# front_pane_-_v2.net
KiCad netlist of a schematic drawn in EAGLE
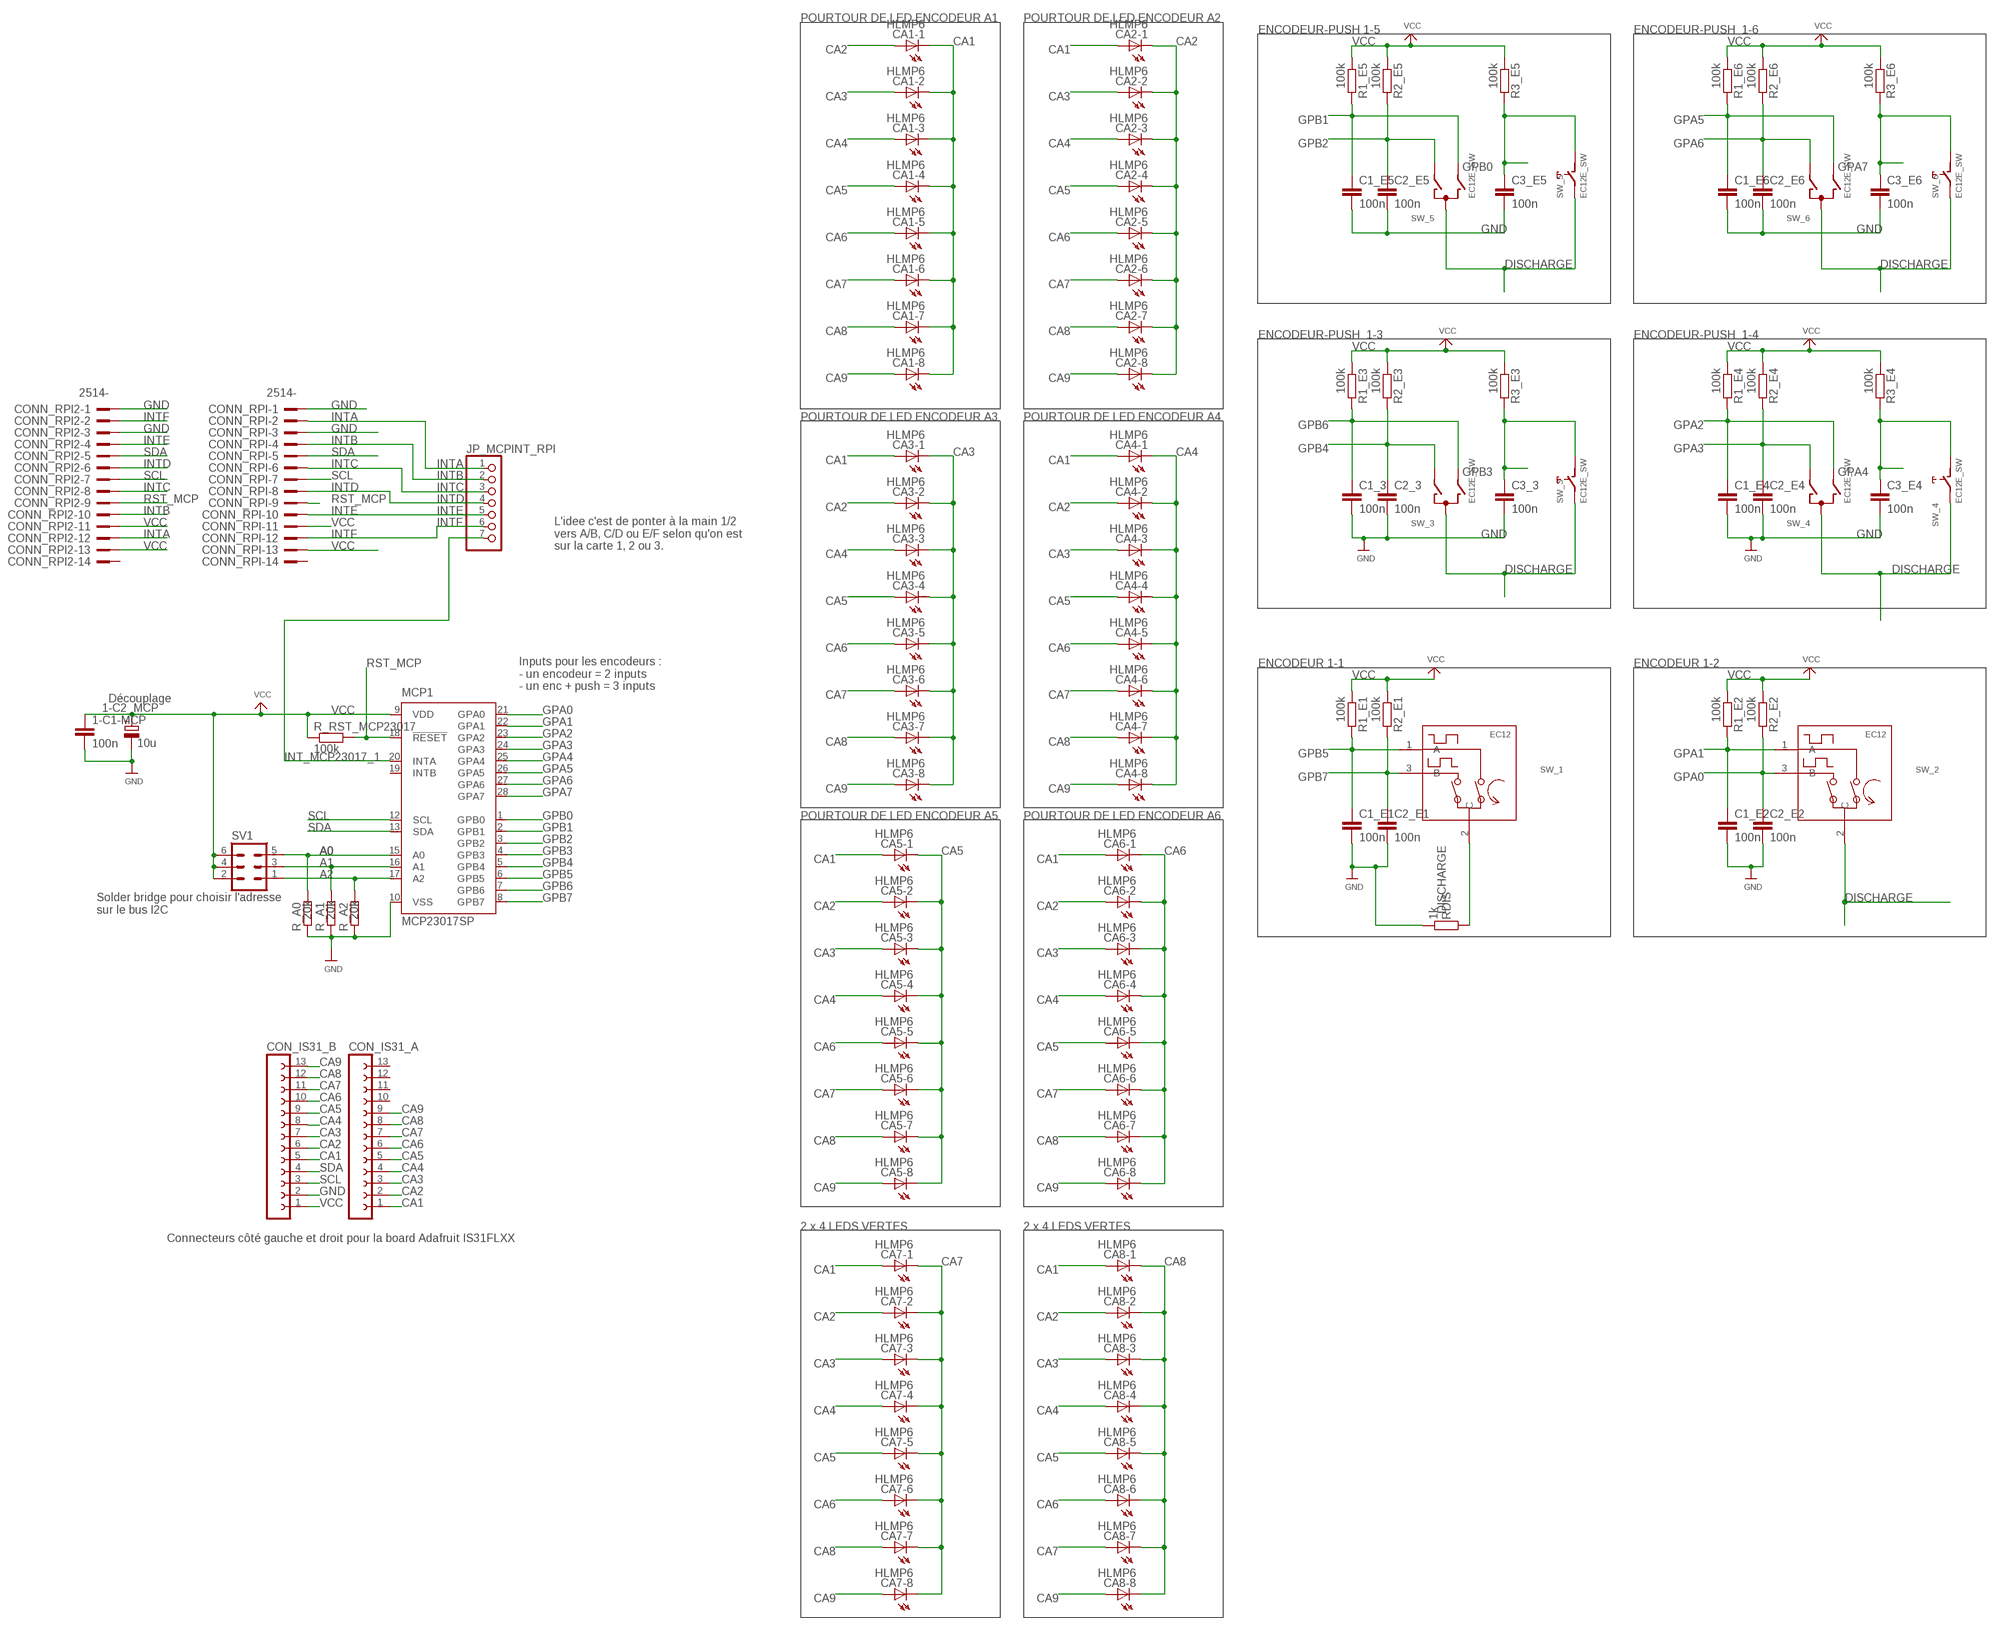
[diagram p0: schematic, sheet 1]

(export (version "E")
  (design (tool "Eeschema 10.0.6"))
  (components
    (comp (ref "1-C1-MCP")
      (value "100n")
      (footprint "eagle-import:C025-024X044")
      (libsource (lib "eagle-import") (part "C-EU025-024X044"))
    )
    (comp (ref "1-C2_MCP")
      (value "10u")
      (footprint "eagle-import:B45181B")
      (libsource (lib "eagle-import") (part "CPOL-EUB45181B"))
    )
    (comp (ref "C1_3")
      (value "100n")
      (footprint "eagle-import:C025-024X044")
      (libsource (lib "eagle-import") (part "C-EU025-024X044"))
    )
    (comp (ref "C1_E1")
      (value "100n")
      (footprint "eagle-import:C025-024X044")
      (libsource (lib "eagle-import") (part "C-EU025-024X044"))
    )
    (comp (ref "C1_E2")
      (value "100n")
      (footprint "eagle-import:C025-024X044")
      (libsource (lib "eagle-import") (part "C-EU025-024X044"))
    )
    (comp (ref "C1_E4")
      (value "100n")
      (footprint "eagle-import:C050-024X044")
      (libsource (lib "eagle-import") (part "C-EU050-024X044"))
    )
    (comp (ref "C1_E5")
      (value "100n")
      (footprint "eagle-import:C025-024X044")
      (libsource (lib "eagle-import") (part "C-EU025-024X044"))
    )
    (comp (ref "C1_E6")
      (value "100n")
      (footprint "eagle-import:C025-024X044")
      (libsource (lib "eagle-import") (part "C-EU025-024X044"))
    )
    (comp (ref "C2_3")
      (value "100n")
      (footprint "eagle-import:C025-024X044")
      (libsource (lib "eagle-import") (part "C-EU025-024X044"))
    )
    (comp (ref "C2_E1")
      (value "100n")
      (footprint "eagle-import:C025-024X044")
      (libsource (lib "eagle-import") (part "C-EU025-024X044"))
    )
    (comp (ref "C2_E2")
      (value "100n")
      (footprint "eagle-import:C025-024X044")
      (libsource (lib "eagle-import") (part "C-EU025-024X044"))
    )
    (comp (ref "C2_E4")
      (value "100n")
      (footprint "eagle-import:C025-024X044")
      (libsource (lib "eagle-import") (part "C-EU025-024X044"))
    )
    (comp (ref "C2_E5")
      (value "100n")
      (footprint "eagle-import:C025-024X044")
      (libsource (lib "eagle-import") (part "C-EU025-024X044"))
    )
    (comp (ref "C2_E6")
      (value "100n")
      (footprint "eagle-import:C025-024X044")
      (libsource (lib "eagle-import") (part "C-EU025-024X044"))
    )
    (comp (ref "C3_3")
      (value "100n")
      (footprint "eagle-import:C025-024X044")
      (libsource (lib "eagle-import") (part "C-EU025-024X044"))
    )
    (comp (ref "C3_E4")
      (value "100n")
      (footprint "eagle-import:C025-024X044")
      (libsource (lib "eagle-import") (part "C-EU025-024X044"))
    )
    (comp (ref "C3_E5")
      (value "100n")
      (footprint "eagle-import:C025-024X044")
      (libsource (lib "eagle-import") (part "C-EU025-024X044"))
    )
    (comp (ref "C3_E6")
      (value "100n")
      (footprint "eagle-import:C025-024X044")
      (libsource (lib "eagle-import") (part "C-EU025-024X044"))
    )
    (comp (ref "CA1-1")
      (value "HLMP6")
      (footprint "eagle-import:HLMP6")
      (fields (field (name "MF") "AGILENT TECHNOLOGIES") (field (name "MPN") "HLMP-6500"))
      (libsource (lib "eagle-import") (part "HLMP6"))
    )
    (comp (ref "CA1-2")
      (value "HLMP6")
      (footprint "eagle-import:HLMP6")
      (fields (field (name "MF") "AGILENT TECHNOLOGIES") (field (name "MPN") "HLMP-6500"))
      (libsource (lib "eagle-import") (part "HLMP6"))
    )
    (comp (ref "CA1-3")
      (value "HLMP6")
      (footprint "eagle-import:HLMP6")
      (fields (field (name "MF") "AGILENT TECHNOLOGIES") (field (name "MPN") "HLMP-6500"))
      (libsource (lib "eagle-import") (part "HLMP6"))
    )
    (comp (ref "CA1-4")
      (value "HLMP6")
      (footprint "eagle-import:HLMP6")
      (fields (field (name "MF") "AGILENT TECHNOLOGIES") (field (name "MPN") "HLMP-6500"))
      (libsource (lib "eagle-import") (part "HLMP6"))
    )
    (comp (ref "CA1-5")
      (value "HLMP6")
      (footprint "eagle-import:HLMP6")
      (fields (field (name "MF") "AGILENT TECHNOLOGIES") (field (name "MPN") "HLMP-6500"))
      (libsource (lib "eagle-import") (part "HLMP6"))
    )
    (comp (ref "CA1-6")
      (value "HLMP6")
      (footprint "eagle-import:HLMP6")
      (fields (field (name "MF") "AGILENT TECHNOLOGIES") (field (name "MPN") "HLMP-6500"))
      (libsource (lib "eagle-import") (part "HLMP6"))
    )
    (comp (ref "CA1-7")
      (value "HLMP6")
      (footprint "eagle-import:HLMP6")
      (fields (field (name "MF") "AGILENT TECHNOLOGIES") (field (name "MPN") "HLMP-6500"))
      (libsource (lib "eagle-import") (part "HLMP6"))
    )
    (comp (ref "CA1-8")
      (value "HLMP6")
      (footprint "eagle-import:HLMP6")
      (fields (field (name "MF") "AGILENT TECHNOLOGIES") (field (name "MPN") "HLMP-6500"))
      (libsource (lib "eagle-import") (part "HLMP6"))
    )
    (comp (ref "CA2-1")
      (value "HLMP6")
      (footprint "eagle-import:HLMP6")
      (fields (field (name "MF") "AGILENT TECHNOLOGIES") (field (name "MPN") "HLMP-6500"))
      (libsource (lib "eagle-import") (part "HLMP6"))
    )
    (comp (ref "CA2-2")
      (value "HLMP6")
      (footprint "eagle-import:HLMP6")
      (fields (field (name "MF") "AGILENT TECHNOLOGIES") (field (name "MPN") "HLMP-6500"))
      (libsource (lib "eagle-import") (part "HLMP6"))
    )
    (comp (ref "CA2-3")
      (value "HLMP6")
      (footprint "eagle-import:HLMP6")
      (fields (field (name "MF") "AGILENT TECHNOLOGIES") (field (name "MPN") "HLMP-6500"))
      (libsource (lib "eagle-import") (part "HLMP6"))
    )
    (comp (ref "CA2-4")
      (value "HLMP6")
      (footprint "eagle-import:HLMP6")
      (fields (field (name "MF") "AGILENT TECHNOLOGIES") (field (name "MPN") "HLMP-6500"))
      (libsource (lib "eagle-import") (part "HLMP6"))
    )
    (comp (ref "CA2-5")
      (value "HLMP6")
      (footprint "eagle-import:HLMP6")
      (fields (field (name "MF") "AGILENT TECHNOLOGIES") (field (name "MPN") "HLMP-6500"))
      (libsource (lib "eagle-import") (part "HLMP6"))
    )
    (comp (ref "CA2-6")
      (value "HLMP6")
      (footprint "eagle-import:HLMP6")
      (fields (field (name "MF") "AGILENT TECHNOLOGIES") (field (name "MPN") "HLMP-6500"))
      (libsource (lib "eagle-import") (part "HLMP6"))
    )
    (comp (ref "CA2-7")
      (value "HLMP6")
      (footprint "eagle-import:HLMP6")
      (fields (field (name "MF") "AGILENT TECHNOLOGIES") (field (name "MPN") "HLMP-6500"))
      (libsource (lib "eagle-import") (part "HLMP6"))
    )
    (comp (ref "CA2-8")
      (value "HLMP6")
      (footprint "eagle-import:HLMP6")
      (fields (field (name "MF") "AGILENT TECHNOLOGIES") (field (name "MPN") "HLMP-6500"))
      (libsource (lib "eagle-import") (part "HLMP6"))
    )
    (comp (ref "CA3-1")
      (value "HLMP6")
      (footprint "eagle-import:HLMP6")
      (fields (field (name "MF") "AGILENT TECHNOLOGIES") (field (name "MPN") "HLMP-6500"))
      (libsource (lib "eagle-import") (part "HLMP6"))
    )
    (comp (ref "CA3-2")
      (value "HLMP6")
      (footprint "eagle-import:HLMP6")
      (fields (field (name "MF") "AGILENT TECHNOLOGIES") (field (name "MPN") "HLMP-6500"))
      (libsource (lib "eagle-import") (part "HLMP6"))
    )
    (comp (ref "CA3-3")
      (value "HLMP6")
      (footprint "eagle-import:HLMP6")
      (fields (field (name "MF") "AGILENT TECHNOLOGIES") (field (name "MPN") "HLMP-6500"))
      (libsource (lib "eagle-import") (part "HLMP6"))
    )
    (comp (ref "CA3-4")
      (value "HLMP6")
      (footprint "eagle-import:HLMP6")
      (fields (field (name "MF") "AGILENT TECHNOLOGIES") (field (name "MPN") "HLMP-6500"))
      (libsource (lib "eagle-import") (part "HLMP6"))
    )
    (comp (ref "CA3-5")
      (value "HLMP6")
      (footprint "eagle-import:HLMP6")
      (fields (field (name "MF") "AGILENT TECHNOLOGIES") (field (name "MPN") "HLMP-6500"))
      (libsource (lib "eagle-import") (part "HLMP6"))
    )
    (comp (ref "CA3-6")
      (value "HLMP6")
      (footprint "eagle-import:HLMP6")
      (fields (field (name "MF") "AGILENT TECHNOLOGIES") (field (name "MPN") "HLMP-6500"))
      (libsource (lib "eagle-import") (part "HLMP6"))
    )
    (comp (ref "CA3-7")
      (value "HLMP6")
      (footprint "eagle-import:HLMP6")
      (fields (field (name "MF") "AGILENT TECHNOLOGIES") (field (name "MPN") "HLMP-6500"))
      (libsource (lib "eagle-import") (part "HLMP6"))
    )
    (comp (ref "CA3-8")
      (value "HLMP6")
      (footprint "eagle-import:HLMP6")
      (fields (field (name "MF") "AGILENT TECHNOLOGIES") (field (name "MPN") "HLMP-6500"))
      (libsource (lib "eagle-import") (part "HLMP6"))
    )
    (comp (ref "CA4-1")
      (value "HLMP6")
      (footprint "eagle-import:HLMP6")
      (fields (field (name "MF") "AGILENT TECHNOLOGIES") (field (name "MPN") "HLMP-6500"))
      (libsource (lib "eagle-import") (part "HLMP6"))
    )
    (comp (ref "CA4-2")
      (value "HLMP6")
      (footprint "eagle-import:HLMP6")
      (fields (field (name "MF") "AGILENT TECHNOLOGIES") (field (name "MPN") "HLMP-6500"))
      (libsource (lib "eagle-import") (part "HLMP6"))
    )
    (comp (ref "CA4-3")
      (value "HLMP6")
      (footprint "eagle-import:HLMP6")
      (fields (field (name "MF") "AGILENT TECHNOLOGIES") (field (name "MPN") "HLMP-6500"))
      (libsource (lib "eagle-import") (part "HLMP6"))
    )
    (comp (ref "CA4-4")
      (value "HLMP6")
      (footprint "eagle-import:HLMP6")
      (fields (field (name "MF") "AGILENT TECHNOLOGIES") (field (name "MPN") "HLMP-6500"))
      (libsource (lib "eagle-import") (part "HLMP6"))
    )
    (comp (ref "CA4-5")
      (value "HLMP6")
      (footprint "eagle-import:HLMP6")
      (fields (field (name "MF") "AGILENT TECHNOLOGIES") (field (name "MPN") "HLMP-6500"))
      (libsource (lib "eagle-import") (part "HLMP6"))
    )
    (comp (ref "CA4-6")
      (value "HLMP6")
      (footprint "eagle-import:HLMP6")
      (fields (field (name "MF") "AGILENT TECHNOLOGIES") (field (name "MPN") "HLMP-6500"))
      (libsource (lib "eagle-import") (part "HLMP6"))
    )
    (comp (ref "CA4-7")
      (value "HLMP6")
      (footprint "eagle-import:HLMP6")
      (fields (field (name "MF") "AGILENT TECHNOLOGIES") (field (name "MPN") "HLMP-6500"))
      (libsource (lib "eagle-import") (part "HLMP6"))
    )
    (comp (ref "CA4-8")
      (value "HLMP6")
      (footprint "eagle-import:HLMP6")
      (fields (field (name "MF") "AGILENT TECHNOLOGIES") (field (name "MPN") "HLMP-6500"))
      (libsource (lib "eagle-import") (part "HLMP6"))
    )
    (comp (ref "CA5-1")
      (value "HLMP6")
      (footprint "eagle-import:HLMP6")
      (fields (field (name "MF") "AGILENT TECHNOLOGIES") (field (name "MPN") "HLMP-6500"))
      (libsource (lib "eagle-import") (part "HLMP6"))
    )
    (comp (ref "CA5-2")
      (value "HLMP6")
      (footprint "eagle-import:HLMP6")
      (fields (field (name "MF") "AGILENT TECHNOLOGIES") (field (name "MPN") "HLMP-6500"))
      (libsource (lib "eagle-import") (part "HLMP6"))
    )
    (comp (ref "CA5-3")
      (value "HLMP6")
      (footprint "eagle-import:HLMP6")
      (fields (field (name "MF") "AGILENT TECHNOLOGIES") (field (name "MPN") "HLMP-6500"))
      (libsource (lib "eagle-import") (part "HLMP6"))
    )
    (comp (ref "CA5-4")
      (value "HLMP6")
      (footprint "eagle-import:HLMP6")
      (fields (field (name "MF") "AGILENT TECHNOLOGIES") (field (name "MPN") "HLMP-6500"))
      (libsource (lib "eagle-import") (part "HLMP6"))
    )
    (comp (ref "CA5-5")
      (value "HLMP6")
      (footprint "eagle-import:HLMP6")
      (fields (field (name "MF") "AGILENT TECHNOLOGIES") (field (name "MPN") "HLMP-6500"))
      (libsource (lib "eagle-import") (part "HLMP6"))
    )
    (comp (ref "CA5-6")
      (value "HLMP6")
      (footprint "eagle-import:HLMP6")
      (fields (field (name "MF") "AGILENT TECHNOLOGIES") (field (name "MPN") "HLMP-6500"))
      (libsource (lib "eagle-import") (part "HLMP6"))
    )
    (comp (ref "CA5-7")
      (value "HLMP6")
      (footprint "eagle-import:HLMP6")
      (fields (field (name "MF") "AGILENT TECHNOLOGIES") (field (name "MPN") "HLMP-6500"))
      (libsource (lib "eagle-import") (part "HLMP6"))
    )
    (comp (ref "CA5-8")
      (value "HLMP6")
      (footprint "eagle-import:HLMP6")
      (fields (field (name "MF") "AGILENT TECHNOLOGIES") (field (name "MPN") "HLMP-6500"))
      (libsource (lib "eagle-import") (part "HLMP6"))
    )
    (comp (ref "CA6-1")
      (value "HLMP6")
      (footprint "eagle-import:HLMP6")
      (fields (field (name "MF") "AGILENT TECHNOLOGIES") (field (name "MPN") "HLMP-6500"))
      (libsource (lib "eagle-import") (part "HLMP6"))
    )
    (comp (ref "CA6-2")
      (value "HLMP6")
      (footprint "eagle-import:HLMP6")
      (fields (field (name "MF") "AGILENT TECHNOLOGIES") (field (name "MPN") "HLMP-6500"))
      (libsource (lib "eagle-import") (part "HLMP6"))
    )
    (comp (ref "CA6-3")
      (value "HLMP6")
      (footprint "eagle-import:HLMP6")
      (fields (field (name "MF") "AGILENT TECHNOLOGIES") (field (name "MPN") "HLMP-6500"))
      (libsource (lib "eagle-import") (part "HLMP6"))
    )
    (comp (ref "CA6-4")
      (value "HLMP6")
      (footprint "eagle-import:HLMP6")
      (fields (field (name "MF") "AGILENT TECHNOLOGIES") (field (name "MPN") "HLMP-6500"))
      (libsource (lib "eagle-import") (part "HLMP6"))
    )
    (comp (ref "CA6-5")
      (value "HLMP6")
      (footprint "eagle-import:HLMP6")
      (fields (field (name "MF") "AGILENT TECHNOLOGIES") (field (name "MPN") "HLMP-6500"))
      (libsource (lib "eagle-import") (part "HLMP6"))
    )
    (comp (ref "CA6-6")
      (value "HLMP6")
      (footprint "eagle-import:HLMP6")
      (fields (field (name "MF") "AGILENT TECHNOLOGIES") (field (name "MPN") "HLMP-6500"))
      (libsource (lib "eagle-import") (part "HLMP6"))
    )
    (comp (ref "CA6-7")
      (value "HLMP6")
      (footprint "eagle-import:HLMP6")
      (fields (field (name "MF") "AGILENT TECHNOLOGIES") (field (name "MPN") "HLMP-6500"))
      (libsource (lib "eagle-import") (part "HLMP6"))
    )
    (comp (ref "CA6-8")
      (value "HLMP6")
      (footprint "eagle-import:HLMP6")
      (fields (field (name "MF") "AGILENT TECHNOLOGIES") (field (name "MPN") "HLMP-6500"))
      (libsource (lib "eagle-import") (part "HLMP6"))
    )
    (comp (ref "CA7-1")
      (value "HLMP6")
      (footprint "eagle-import:HLMP6")
      (fields (field (name "MF") "AGILENT TECHNOLOGIES") (field (name "MPN") "HLMP-6500"))
      (libsource (lib "eagle-import") (part "HLMP6"))
    )
    (comp (ref "CA7-2")
      (value "HLMP6")
      (footprint "eagle-import:HLMP6")
      (fields (field (name "MF") "AGILENT TECHNOLOGIES") (field (name "MPN") "HLMP-6500"))
      (libsource (lib "eagle-import") (part "HLMP6"))
    )
    (comp (ref "CA7-3")
      (value "HLMP6")
      (footprint "eagle-import:HLMP6")
      (fields (field (name "MF") "AGILENT TECHNOLOGIES") (field (name "MPN") "HLMP-6500"))
      (libsource (lib "eagle-import") (part "HLMP6"))
    )
    (comp (ref "CA7-4")
      (value "HLMP6")
      (footprint "eagle-import:HLMP6")
      (fields (field (name "MF") "AGILENT TECHNOLOGIES") (field (name "MPN") "HLMP-6500"))
      (libsource (lib "eagle-import") (part "HLMP6"))
    )
    (comp (ref "CA7-5")
      (value "HLMP6")
      (footprint "eagle-import:HLMP6")
      (fields (field (name "MF") "AGILENT TECHNOLOGIES") (field (name "MPN") "HLMP-6500"))
      (libsource (lib "eagle-import") (part "HLMP6"))
    )
    (comp (ref "CA7-6")
      (value "HLMP6")
      (footprint "eagle-import:HLMP6")
      (fields (field (name "MF") "AGILENT TECHNOLOGIES") (field (name "MPN") "HLMP-6500"))
      (libsource (lib "eagle-import") (part "HLMP6"))
    )
    (comp (ref "CA7-7")
      (value "HLMP6")
      (footprint "eagle-import:HLMP6")
      (fields (field (name "MF") "AGILENT TECHNOLOGIES") (field (name "MPN") "HLMP-6500"))
      (libsource (lib "eagle-import") (part "HLMP6"))
    )
    (comp (ref "CA7-8")
      (value "HLMP6")
      (footprint "eagle-import:HLMP6")
      (fields (field (name "MF") "AGILENT TECHNOLOGIES") (field (name "MPN") "HLMP-6500"))
      (libsource (lib "eagle-import") (part "HLMP6"))
    )
    (comp (ref "CA8-1")
      (value "HLMP6")
      (footprint "eagle-import:HLMP6")
      (fields (field (name "MF") "AGILENT TECHNOLOGIES") (field (name "MPN") "HLMP-6500"))
      (libsource (lib "eagle-import") (part "HLMP6"))
    )
    (comp (ref "CA8-2")
      (value "HLMP6")
      (footprint "eagle-import:HLMP6")
      (fields (field (name "MF") "AGILENT TECHNOLOGIES") (field (name "MPN") "HLMP-6500"))
      (libsource (lib "eagle-import") (part "HLMP6"))
    )
    (comp (ref "CA8-3")
      (value "HLMP6")
      (footprint "eagle-import:HLMP6")
      (fields (field (name "MF") "AGILENT TECHNOLOGIES") (field (name "MPN") "HLMP-6500"))
      (libsource (lib "eagle-import") (part "HLMP6"))
    )
    (comp (ref "CA8-4")
      (value "HLMP6")
      (footprint "eagle-import:HLMP6")
      (fields (field (name "MF") "AGILENT TECHNOLOGIES") (field (name "MPN") "HLMP-6500"))
      (libsource (lib "eagle-import") (part "HLMP6"))
    )
    (comp (ref "CA8-5")
      (value "HLMP6")
      (footprint "eagle-import:HLMP6")
      (fields (field (name "MF") "AGILENT TECHNOLOGIES") (field (name "MPN") "HLMP-6500"))
      (libsource (lib "eagle-import") (part "HLMP6"))
    )
    (comp (ref "CA8-6")
      (value "HLMP6")
      (footprint "eagle-import:HLMP6")
      (fields (field (name "MF") "AGILENT TECHNOLOGIES") (field (name "MPN") "HLMP-6500"))
      (libsource (lib "eagle-import") (part "HLMP6"))
    )
    (comp (ref "CA8-7")
      (value "HLMP6")
      (footprint "eagle-import:HLMP6")
      (fields (field (name "MF") "AGILENT TECHNOLOGIES") (field (name "MPN") "HLMP-6500"))
      (libsource (lib "eagle-import") (part "HLMP6"))
    )
    (comp (ref "CA8-8")
      (value "HLMP6")
      (footprint "eagle-import:HLMP6")
      (fields (field (name "MF") "AGILENT TECHNOLOGIES") (field (name "MPN") "HLMP-6500"))
      (libsource (lib "eagle-import") (part "HLMP6"))
    )
    (comp (ref "CONN_RPI")
      (value "2514-")
      (footprint "eagle-import:PAK100_2500-14")
      (libsource (lib "eagle-import") (part "2514-"))
    )
    (comp (ref "CONN_RPI2")
      (value "2514-")
      (footprint "eagle-import:PAK100_2500-14")
      (libsource (lib "eagle-import") (part "2514-"))
    )
    (comp (ref "CON_IS31_A")
      (value "FE13-1")
      (footprint "eagle-import:FE13")
      (libsource (lib "eagle-import") (part "FE13-1"))
    )
    (comp (ref "CON_IS31_B")
      (value "FE13-1")
      (footprint "eagle-import:FE13")
      (libsource (lib "eagle-import") (part "FE13-1"))
    )
    (comp (ref "JP_MCPINT_RPI")
      (value "PINHD-1X7")
      (footprint "eagle-import:1X07")
      (libsource (lib "eagle-import") (part "PINHD-1X7"))
    )
    (comp (ref "MCP1")
      (value "MCP23017SP")
      (footprint "eagle-import:DIL28-3")
      (fields (field (name "MF") "MICROCHIP") (field (name "MPN") "MCP23017-E/SP"))
      (libsource (lib "eagle-import") (part "MCP23017SP"))
    )
    (comp (ref "R1_E1")
      (value "100k")
      (footprint "eagle-import:0204_5")
      (libsource (lib "eagle-import") (part "R-EU_0204/5"))
    )
    (comp (ref "R1_E2")
      (value "100k")
      (footprint "eagle-import:0204_5")
      (libsource (lib "eagle-import") (part "R-EU_0204/5"))
    )
    (comp (ref "R1_E3")
      (value "100k")
      (footprint "eagle-import:0204_5")
      (libsource (lib "eagle-import") (part "R-EU_0204/5"))
    )
    (comp (ref "R1_E4")
      (value "100k")
      (footprint "eagle-import:0204_5")
      (libsource (lib "eagle-import") (part "R-EU_0204/5"))
    )
    (comp (ref "R1_E5")
      (value "100k")
      (footprint "eagle-import:0204_5")
      (libsource (lib "eagle-import") (part "R-EU_0204/5"))
    )
    (comp (ref "R1_E6")
      (value "100k")
      (footprint "eagle-import:0204_5")
      (libsource (lib "eagle-import") (part "R-EU_0204/5"))
    )
    (comp (ref "R2_E1")
      (value "100k")
      (footprint "eagle-import:0204_5")
      (libsource (lib "eagle-import") (part "R-EU_0204/5"))
    )
    (comp (ref "R2_E2")
      (value "100k")
      (footprint "eagle-import:0204_5")
      (libsource (lib "eagle-import") (part "R-EU_0204/5"))
    )
    (comp (ref "R2_E3")
      (value "100k")
      (footprint "eagle-import:0204_5")
      (libsource (lib "eagle-import") (part "R-EU_0204/5"))
    )
    (comp (ref "R2_E4")
      (value "100k")
      (footprint "eagle-import:0204_5")
      (libsource (lib "eagle-import") (part "R-EU_0204/5"))
    )
    (comp (ref "R2_E5")
      (value "100k")
      (footprint "eagle-import:0204_5")
      (libsource (lib "eagle-import") (part "R-EU_0204/5"))
    )
    (comp (ref "R2_E6")
      (value "100k")
      (footprint "eagle-import:0204_5")
      (libsource (lib "eagle-import") (part "R-EU_0204/5"))
    )
    (comp (ref "R3_E3")
      (value "100k")
      (footprint "eagle-import:0204_5")
      (libsource (lib "eagle-import") (part "R-EU_0204/5"))
    )
    (comp (ref "R3_E4")
      (value "100k")
      (footprint "eagle-import:0204_5")
      (libsource (lib "eagle-import") (part "R-EU_0204/5"))
    )
    (comp (ref "R3_E5")
      (value "100k")
      (footprint "eagle-import:0204_5")
      (libsource (lib "eagle-import") (part "R-EU_0204/5"))
    )
    (comp (ref "R3_E6")
      (value "100k")
      (footprint "eagle-import:0204_5")
      (libsource (lib "eagle-import") (part "R-EU_0204/5"))
    )
    (comp (ref "RDIS")
      (value "1k")
      (footprint "eagle-import:0204_5")
      (libsource (lib "eagle-import") (part "R-EU_0204/5"))
    )
    (comp (ref "R_A0")
      (value "20k")
      (footprint "eagle-import:0204_5")
      (libsource (lib "eagle-import") (part "R-EU_0204/5"))
    )
    (comp (ref "R_A1")
      (value "20k")
      (footprint "eagle-import:0204_5")
      (libsource (lib "eagle-import") (part "R-EU_0204/5"))
    )
    (comp (ref "R_A2")
      (value "20k")
      (footprint "eagle-import:0204_5")
      (libsource (lib "eagle-import") (part "R-EU_0204/5"))
    )
    (comp (ref "R_RST_MCP23017")
      (value "100k")
      (footprint "eagle-import:0204_5")
      (libsource (lib "eagle-import") (part "R-EU_0204/5"))
    )
    (comp (ref "SV1")
      (value "MA03-2")
      (footprint "eagle-import:MA03-2")
      (libsource (lib "eagle-import") (part "MA03-2"))
    )
    (comp (ref "SW_1")
      (value "EC12")
      (footprint "eagle-import:EC12")
      (libsource (lib "eagle-import") (part "EC12"))
    )
    (comp (ref "SW_2")
      (value "EC12")
      (footprint "eagle-import:EC12")
      (libsource (lib "eagle-import") (part "EC12"))
    )
    (comp (ref "SW_3")
      (value "EC12E_SW")
      (footprint "eagle-import:ALPS_EC12E_SW")
      (fields (field (name "MPN") "EC12E2424407"))
      (libsource (lib "eagle-import") (part "EC12E_SW"))
    )
    (comp (ref "SW_4")
      (value "EC12E_SW")
      (footprint "eagle-import:ALPS_EC12E_SW")
      (fields (field (name "MPN") "EC12E2424407"))
      (libsource (lib "eagle-import") (part "EC12E_SW"))
    )
    (comp (ref "SW_5")
      (value "EC12E_SW")
      (footprint "eagle-import:ALPS_EC12E_SW")
      (fields (field (name "MPN") "EC12E2424407"))
      (libsource (lib "eagle-import") (part "EC12E_SW"))
    )
    (comp (ref "SW_6")
      (value "EC12E_SW")
      (footprint "eagle-import:ALPS_EC12E_SW")
      (fields (field (name "MPN") "EC12E2424407"))
      (libsource (lib "eagle-import") (part "EC12E_SW"))
    )
  )
  (nets
    (net (code "1") (name "/A0") (class "Default")
      (node (ref "MCP1") (pin "15") (pinfunction "A0_15") (pintype "input"))
      (node (ref "R_A0") (pin "2") (pinfunction "2_2") (pintype "passive"))
      (node (ref "SV1") (pin "5") (pinfunction "5_5") (pintype "passive"))
    )
    (net (code "2") (name "/A1") (class "Default")
      (node (ref "MCP1") (pin "16") (pinfunction "A1_16") (pintype "input"))
      (node (ref "R_A1") (pin "2") (pinfunction "2_2") (pintype "passive"))
      (node (ref "SV1") (pin "3") (pinfunction "3_3") (pintype "passive"))
    )
    (net (code "3") (name "/A2") (class "Default")
      (node (ref "MCP1") (pin "17") (pinfunction "A2_17") (pintype "input"))
      (node (ref "R_A2") (pin "2") (pinfunction "2_2") (pintype "passive"))
      (node (ref "SV1") (pin "1") (pinfunction "1_1") (pintype "passive"))
    )
    (net (code "4") (name "/CA1") (class "Default")
      (node (ref "CA1-1") (pin "K") (pinfunction "K_K") (pintype "passive"))
      (node (ref "CA1-2") (pin "K") (pinfunction "K_K") (pintype "passive"))
      (node (ref "CA1-3") (pin "K") (pinfunction "K_K") (pintype "passive"))
      (node (ref "CA1-4") (pin "K") (pinfunction "K_K") (pintype "passive"))
      (node (ref "CA1-5") (pin "K") (pinfunction "K_K") (pintype "passive"))
      (node (ref "CA1-6") (pin "K") (pinfunction "K_K") (pintype "passive"))
      (node (ref "CA1-7") (pin "K") (pinfunction "K_K") (pintype "passive"))
      (node (ref "CA1-8") (pin "K") (pinfunction "K_K") (pintype "passive"))
      (node (ref "CA2-1") (pin "A") (pinfunction "A_A") (pintype "passive"))
      (node (ref "CA3-1") (pin "A") (pinfunction "A_A") (pintype "passive"))
      (node (ref "CA4-1") (pin "A") (pinfunction "A_A") (pintype "passive"))
      (node (ref "CA5-1") (pin "A") (pinfunction "A_A") (pintype "passive"))
      (node (ref "CA6-1") (pin "A") (pinfunction "A_A") (pintype "passive"))
      (node (ref "CA7-1") (pin "A") (pinfunction "A_A") (pintype "passive"))
      (node (ref "CA8-1") (pin "A") (pinfunction "A_A") (pintype "passive"))
      (node (ref "CON_IS31_A") (pin "1") (pinfunction "1_1") (pintype "passive"))
      (node (ref "CON_IS31_B") (pin "5") (pinfunction "5_5") (pintype "passive"))
    )
    (net (code "5") (name "/CA2") (class "Default")
      (node (ref "CA1-1") (pin "A") (pinfunction "A_A") (pintype "passive"))
      (node (ref "CA2-1") (pin "K") (pinfunction "K_K") (pintype "passive"))
      (node (ref "CA2-2") (pin "K") (pinfunction "K_K") (pintype "passive"))
      (node (ref "CA2-3") (pin "K") (pinfunction "K_K") (pintype "passive"))
      (node (ref "CA2-4") (pin "K") (pinfunction "K_K") (pintype "passive"))
      (node (ref "CA2-5") (pin "K") (pinfunction "K_K") (pintype "passive"))
      (node (ref "CA2-6") (pin "K") (pinfunction "K_K") (pintype "passive"))
      (node (ref "CA2-7") (pin "K") (pinfunction "K_K") (pintype "passive"))
      (node (ref "CA2-8") (pin "K") (pinfunction "K_K") (pintype "passive"))
      (node (ref "CA3-2") (pin "A") (pinfunction "A_A") (pintype "passive"))
      (node (ref "CA4-2") (pin "A") (pinfunction "A_A") (pintype "passive"))
      (node (ref "CA5-2") (pin "A") (pinfunction "A_A") (pintype "passive"))
      (node (ref "CA6-2") (pin "A") (pinfunction "A_A") (pintype "passive"))
      (node (ref "CA7-2") (pin "A") (pinfunction "A_A") (pintype "passive"))
      (node (ref "CA8-2") (pin "A") (pinfunction "A_A") (pintype "passive"))
      (node (ref "CON_IS31_A") (pin "2") (pinfunction "2_2") (pintype "passive"))
      (node (ref "CON_IS31_B") (pin "6") (pinfunction "6_6") (pintype "passive"))
    )
    (net (code "6") (name "/CA3") (class "Default")
      (node (ref "CA1-2") (pin "A") (pinfunction "A_A") (pintype "passive"))
      (node (ref "CA2-2") (pin "A") (pinfunction "A_A") (pintype "passive"))
      (node (ref "CA3-1") (pin "K") (pinfunction "K_K") (pintype "passive"))
      (node (ref "CA3-2") (pin "K") (pinfunction "K_K") (pintype "passive"))
      (node (ref "CA3-3") (pin "K") (pinfunction "K_K") (pintype "passive"))
      (node (ref "CA3-4") (pin "K") (pinfunction "K_K") (pintype "passive"))
      (node (ref "CA3-5") (pin "K") (pinfunction "K_K") (pintype "passive"))
      (node (ref "CA3-6") (pin "K") (pinfunction "K_K") (pintype "passive"))
      (node (ref "CA3-7") (pin "K") (pinfunction "K_K") (pintype "passive"))
      (node (ref "CA3-8") (pin "K") (pinfunction "K_K") (pintype "passive"))
      (node (ref "CA4-3") (pin "A") (pinfunction "A_A") (pintype "passive"))
      (node (ref "CA5-3") (pin "A") (pinfunction "A_A") (pintype "passive"))
      (node (ref "CA6-3") (pin "A") (pinfunction "A_A") (pintype "passive"))
      (node (ref "CA7-3") (pin "A") (pinfunction "A_A") (pintype "passive"))
      (node (ref "CA8-3") (pin "A") (pinfunction "A_A") (pintype "passive"))
      (node (ref "CON_IS31_A") (pin "3") (pinfunction "3_3") (pintype "passive"))
      (node (ref "CON_IS31_B") (pin "7") (pinfunction "7_7") (pintype "passive"))
    )
    (net (code "7") (name "/CA4") (class "Default")
      (node (ref "CA1-3") (pin "A") (pinfunction "A_A") (pintype "passive"))
      (node (ref "CA2-3") (pin "A") (pinfunction "A_A") (pintype "passive"))
      (node (ref "CA3-3") (pin "A") (pinfunction "A_A") (pintype "passive"))
      (node (ref "CA4-1") (pin "K") (pinfunction "K_K") (pintype "passive"))
      (node (ref "CA4-2") (pin "K") (pinfunction "K_K") (pintype "passive"))
      (node (ref "CA4-3") (pin "K") (pinfunction "K_K") (pintype "passive"))
      (node (ref "CA4-4") (pin "K") (pinfunction "K_K") (pintype "passive"))
      (node (ref "CA4-5") (pin "K") (pinfunction "K_K") (pintype "passive"))
      (node (ref "CA4-6") (pin "K") (pinfunction "K_K") (pintype "passive"))
      (node (ref "CA4-7") (pin "K") (pinfunction "K_K") (pintype "passive"))
      (node (ref "CA4-8") (pin "K") (pinfunction "K_K") (pintype "passive"))
      (node (ref "CA5-4") (pin "A") (pinfunction "A_A") (pintype "passive"))
      (node (ref "CA6-4") (pin "A") (pinfunction "A_A") (pintype "passive"))
      (node (ref "CA7-4") (pin "A") (pinfunction "A_A") (pintype "passive"))
      (node (ref "CA8-4") (pin "A") (pinfunction "A_A") (pintype "passive"))
      (node (ref "CON_IS31_A") (pin "4") (pinfunction "4_4") (pintype "passive"))
      (node (ref "CON_IS31_B") (pin "8") (pinfunction "8_8") (pintype "passive"))
    )
    (net (code "8") (name "/CA5") (class "Default")
      (node (ref "CA1-4") (pin "A") (pinfunction "A_A") (pintype "passive"))
      (node (ref "CA2-4") (pin "A") (pinfunction "A_A") (pintype "passive"))
      (node (ref "CA3-4") (pin "A") (pinfunction "A_A") (pintype "passive"))
      (node (ref "CA4-4") (pin "A") (pinfunction "A_A") (pintype "passive"))
      (node (ref "CA5-1") (pin "K") (pinfunction "K_K") (pintype "passive"))
      (node (ref "CA5-2") (pin "K") (pinfunction "K_K") (pintype "passive"))
      (node (ref "CA5-3") (pin "K") (pinfunction "K_K") (pintype "passive"))
      (node (ref "CA5-4") (pin "K") (pinfunction "K_K") (pintype "passive"))
      (node (ref "CA5-5") (pin "K") (pinfunction "K_K") (pintype "passive"))
      (node (ref "CA5-6") (pin "K") (pinfunction "K_K") (pintype "passive"))
      (node (ref "CA5-7") (pin "K") (pinfunction "K_K") (pintype "passive"))
      (node (ref "CA5-8") (pin "K") (pinfunction "K_K") (pintype "passive"))
      (node (ref "CA6-5") (pin "A") (pinfunction "A_A") (pintype "passive"))
      (node (ref "CA7-5") (pin "A") (pinfunction "A_A") (pintype "passive"))
      (node (ref "CA8-5") (pin "A") (pinfunction "A_A") (pintype "passive"))
      (node (ref "CON_IS31_A") (pin "5") (pinfunction "5_5") (pintype "passive"))
      (node (ref "CON_IS31_B") (pin "9") (pinfunction "9_9") (pintype "passive"))
    )
    (net (code "9") (name "/CA6") (class "Default")
      (node (ref "CA1-5") (pin "A") (pinfunction "A_A") (pintype "passive"))
      (node (ref "CA2-5") (pin "A") (pinfunction "A_A") (pintype "passive"))
      (node (ref "CA3-5") (pin "A") (pinfunction "A_A") (pintype "passive"))
      (node (ref "CA4-5") (pin "A") (pinfunction "A_A") (pintype "passive"))
      (node (ref "CA5-5") (pin "A") (pinfunction "A_A") (pintype "passive"))
      (node (ref "CA6-1") (pin "K") (pinfunction "K_K") (pintype "passive"))
      (node (ref "CA6-2") (pin "K") (pinfunction "K_K") (pintype "passive"))
      (node (ref "CA6-3") (pin "K") (pinfunction "K_K") (pintype "passive"))
      (node (ref "CA6-4") (pin "K") (pinfunction "K_K") (pintype "passive"))
      (node (ref "CA6-5") (pin "K") (pinfunction "K_K") (pintype "passive"))
      (node (ref "CA6-6") (pin "K") (pinfunction "K_K") (pintype "passive"))
      (node (ref "CA6-7") (pin "K") (pinfunction "K_K") (pintype "passive"))
      (node (ref "CA6-8") (pin "K") (pinfunction "K_K") (pintype "passive"))
      (node (ref "CA7-6") (pin "A") (pinfunction "A_A") (pintype "passive"))
      (node (ref "CA8-6") (pin "A") (pinfunction "A_A") (pintype "passive"))
      (node (ref "CON_IS31_A") (pin "6") (pinfunction "6_6") (pintype "passive"))
      (node (ref "CON_IS31_B") (pin "10") (pinfunction "10_10") (pintype "passive"))
    )
    (net (code "10") (name "/CA7") (class "Default")
      (node (ref "CA1-6") (pin "A") (pinfunction "A_A") (pintype "passive"))
      (node (ref "CA2-6") (pin "A") (pinfunction "A_A") (pintype "passive"))
      (node (ref "CA3-6") (pin "A") (pinfunction "A_A") (pintype "passive"))
      (node (ref "CA4-6") (pin "A") (pinfunction "A_A") (pintype "passive"))
      (node (ref "CA5-6") (pin "A") (pinfunction "A_A") (pintype "passive"))
      (node (ref "CA6-6") (pin "A") (pinfunction "A_A") (pintype "passive"))
      (node (ref "CA7-1") (pin "K") (pinfunction "K_K") (pintype "passive"))
      (node (ref "CA7-2") (pin "K") (pinfunction "K_K") (pintype "passive"))
      (node (ref "CA7-3") (pin "K") (pinfunction "K_K") (pintype "passive"))
      (node (ref "CA7-4") (pin "K") (pinfunction "K_K") (pintype "passive"))
      (node (ref "CA7-5") (pin "K") (pinfunction "K_K") (pintype "passive"))
      (node (ref "CA7-6") (pin "K") (pinfunction "K_K") (pintype "passive"))
      (node (ref "CA7-7") (pin "K") (pinfunction "K_K") (pintype "passive"))
      (node (ref "CA7-8") (pin "K") (pinfunction "K_K") (pintype "passive"))
      (node (ref "CA8-7") (pin "A") (pinfunction "A_A") (pintype "passive"))
      (node (ref "CON_IS31_A") (pin "7") (pinfunction "7_7") (pintype "passive"))
      (node (ref "CON_IS31_B") (pin "11") (pinfunction "11_11") (pintype "passive"))
    )
    (net (code "11") (name "/CA8") (class "Default")
      (node (ref "CA1-7") (pin "A") (pinfunction "A_A") (pintype "passive"))
      (node (ref "CA2-7") (pin "A") (pinfunction "A_A") (pintype "passive"))
      (node (ref "CA3-7") (pin "A") (pinfunction "A_A") (pintype "passive"))
      (node (ref "CA4-7") (pin "A") (pinfunction "A_A") (pintype "passive"))
      (node (ref "CA5-7") (pin "A") (pinfunction "A_A") (pintype "passive"))
      (node (ref "CA6-7") (pin "A") (pinfunction "A_A") (pintype "passive"))
      (node (ref "CA7-7") (pin "A") (pinfunction "A_A") (pintype "passive"))
      (node (ref "CA8-1") (pin "K") (pinfunction "K_K") (pintype "passive"))
      (node (ref "CA8-2") (pin "K") (pinfunction "K_K") (pintype "passive"))
      (node (ref "CA8-3") (pin "K") (pinfunction "K_K") (pintype "passive"))
      (node (ref "CA8-4") (pin "K") (pinfunction "K_K") (pintype "passive"))
      (node (ref "CA8-5") (pin "K") (pinfunction "K_K") (pintype "passive"))
      (node (ref "CA8-6") (pin "K") (pinfunction "K_K") (pintype "passive"))
      (node (ref "CA8-7") (pin "K") (pinfunction "K_K") (pintype "passive"))
      (node (ref "CA8-8") (pin "K") (pinfunction "K_K") (pintype "passive"))
      (node (ref "CON_IS31_A") (pin "8") (pinfunction "8_8") (pintype "passive"))
      (node (ref "CON_IS31_B") (pin "12") (pinfunction "12_12") (pintype "passive"))
    )
    (net (code "12") (name "/CA9") (class "Default")
      (node (ref "CA1-8") (pin "A") (pinfunction "A_A") (pintype "passive"))
      (node (ref "CA2-8") (pin "A") (pinfunction "A_A") (pintype "passive"))
      (node (ref "CA3-8") (pin "A") (pinfunction "A_A") (pintype "passive"))
      (node (ref "CA4-8") (pin "A") (pinfunction "A_A") (pintype "passive"))
      (node (ref "CA5-8") (pin "A") (pinfunction "A_A") (pintype "passive"))
      (node (ref "CA6-8") (pin "A") (pinfunction "A_A") (pintype "passive"))
      (node (ref "CA7-8") (pin "A") (pinfunction "A_A") (pintype "passive"))
      (node (ref "CA8-8") (pin "A") (pinfunction "A_A") (pintype "passive"))
      (node (ref "CON_IS31_A") (pin "9") (pinfunction "9_9") (pintype "passive"))
      (node (ref "CON_IS31_B") (pin "13") (pinfunction "13_13") (pintype "passive"))
    )
    (net (code "13") (name "/DISCHARGE") (class "Default")
      (node (ref "RDIS") (pin "1") (pinfunction "1_1") (pintype "passive"))
      (node (ref "SW_1") (pin "2") (pinfunction "C_2") (pintype "bidirectional"))
      (node (ref "SW_2") (pin "2") (pinfunction "C_2") (pintype "bidirectional"))
      (node (ref "SW_3") (pin "C") (pinfunction "C_C") (pintype "passive"))
      (node (ref "SW_3") (pin "E") (pinfunction "2_E") (pintype "passive"))
      (node (ref "SW_4") (pin "C") (pinfunction "C_C") (pintype "passive"))
      (node (ref "SW_4") (pin "E") (pinfunction "2_E") (pintype "passive"))
      (node (ref "SW_5") (pin "C") (pinfunction "C_C") (pintype "passive"))
      (node (ref "SW_5") (pin "E") (pinfunction "2_E") (pintype "passive"))
      (node (ref "SW_6") (pin "C") (pinfunction "C_C") (pintype "passive"))
      (node (ref "SW_6") (pin "E") (pinfunction "2_E") (pintype "passive"))
    )
    (net (code "14") (name "/GPA0") (class "Default")
      (node (ref "C2_E2") (pin "1") (pinfunction "1_1") (pintype "passive"))
      (node (ref "MCP1") (pin "21") (pinfunction "GPA0_21") (pintype "bidirectional"))
      (node (ref "R2_E2") (pin "2") (pinfunction "2_2") (pintype "passive"))
      (node (ref "SW_2") (pin "3") (pinfunction "B_3") (pintype "bidirectional"))
    )
    (net (code "15") (name "/GPA1") (class "Default")
      (node (ref "C1_E2") (pin "1") (pinfunction "1_1") (pintype "passive"))
      (node (ref "MCP1") (pin "22") (pinfunction "GPA1_22") (pintype "bidirectional"))
      (node (ref "R1_E2") (pin "2") (pinfunction "2_2") (pintype "passive"))
      (node (ref "SW_2") (pin "1") (pinfunction "A_1") (pintype "bidirectional"))
    )
    (net (code "16") (name "/GPA2") (class "Default")
      (node (ref "C1_E4") (pin "1") (pinfunction "1_1") (pintype "passive"))
      (node (ref "MCP1") (pin "23") (pinfunction "GPA2_23") (pintype "bidirectional"))
      (node (ref "R1_E4") (pin "2") (pinfunction "2_2") (pintype "passive"))
      (node (ref "SW_4") (pin "B") (pinfunction "B_B") (pintype "passive"))
    )
    (net (code "17") (name "/GPA3") (class "Default")
      (node (ref "C2_E4") (pin "1") (pinfunction "1_1") (pintype "passive"))
      (node (ref "MCP1") (pin "24") (pinfunction "GPA3_24") (pintype "bidirectional"))
      (node (ref "R2_E4") (pin "2") (pinfunction "2_2") (pintype "passive"))
      (node (ref "SW_4") (pin "A") (pinfunction "A_A") (pintype "passive"))
    )
    (net (code "18") (name "/GPA4") (class "Default")
      (node (ref "C3_E4") (pin "1") (pinfunction "1_1") (pintype "passive"))
      (node (ref "MCP1") (pin "25") (pinfunction "GPA4_25") (pintype "bidirectional"))
      (node (ref "R3_E4") (pin "2") (pinfunction "2_2") (pintype "passive"))
      (node (ref "SW_4") (pin "D") (pinfunction "1_D") (pintype "passive"))
    )
    (net (code "19") (name "/GPA5") (class "Default")
      (node (ref "C1_E6") (pin "1") (pinfunction "1_1") (pintype "passive"))
      (node (ref "MCP1") (pin "26") (pinfunction "GPA5_26") (pintype "bidirectional"))
      (node (ref "R1_E6") (pin "2") (pinfunction "2_2") (pintype "passive"))
      (node (ref "SW_6") (pin "B") (pinfunction "B_B") (pintype "passive"))
    )
    (net (code "20") (name "/GPA6") (class "Default")
      (node (ref "C2_E6") (pin "1") (pinfunction "1_1") (pintype "passive"))
      (node (ref "MCP1") (pin "27") (pinfunction "GPA6_27") (pintype "bidirectional"))
      (node (ref "R2_E6") (pin "2") (pinfunction "2_2") (pintype "passive"))
      (node (ref "SW_6") (pin "A") (pinfunction "A_A") (pintype "passive"))
    )
    (net (code "21") (name "/GPA7") (class "Default")
      (node (ref "C3_E6") (pin "1") (pinfunction "1_1") (pintype "passive"))
      (node (ref "MCP1") (pin "28") (pinfunction "GPA7_28") (pintype "bidirectional"))
      (node (ref "R3_E6") (pin "2") (pinfunction "2_2") (pintype "passive"))
      (node (ref "SW_6") (pin "D") (pinfunction "1_D") (pintype "passive"))
    )
    (net (code "22") (name "/GPB0") (class "Default")
      (node (ref "C3_E5") (pin "1") (pinfunction "1_1") (pintype "passive"))
      (node (ref "MCP1") (pin "1") (pinfunction "GPB0_1") (pintype "bidirectional"))
      (node (ref "R3_E5") (pin "2") (pinfunction "2_2") (pintype "passive"))
      (node (ref "SW_5") (pin "D") (pinfunction "1_D") (pintype "passive"))
    )
    (net (code "23") (name "/GPB1") (class "Default")
      (node (ref "C1_E5") (pin "1") (pinfunction "1_1") (pintype "passive"))
      (node (ref "MCP1") (pin "2") (pinfunction "GPB1_2") (pintype "bidirectional"))
      (node (ref "R1_E5") (pin "2") (pinfunction "2_2") (pintype "passive"))
      (node (ref "SW_5") (pin "B") (pinfunction "B_B") (pintype "passive"))
    )
    (net (code "24") (name "/GPB2") (class "Default")
      (node (ref "C2_E5") (pin "1") (pinfunction "1_1") (pintype "passive"))
      (node (ref "MCP1") (pin "3") (pinfunction "GPB2_3") (pintype "bidirectional"))
      (node (ref "R2_E5") (pin "2") (pinfunction "2_2") (pintype "passive"))
      (node (ref "SW_5") (pin "A") (pinfunction "A_A") (pintype "passive"))
    )
    (net (code "25") (name "/GPB3") (class "Default")
      (node (ref "C3_3") (pin "1") (pinfunction "1_1") (pintype "passive"))
      (node (ref "MCP1") (pin "4") (pinfunction "GPB3_4") (pintype "bidirectional"))
      (node (ref "R3_E3") (pin "2") (pinfunction "2_2") (pintype "passive"))
      (node (ref "SW_3") (pin "D") (pinfunction "1_D") (pintype "passive"))
    )
    (net (code "26") (name "/GPB4") (class "Default")
      (node (ref "C2_3") (pin "1") (pinfunction "1_1") (pintype "passive"))
      (node (ref "MCP1") (pin "5") (pinfunction "GPB4_5") (pintype "bidirectional"))
      (node (ref "R2_E3") (pin "2") (pinfunction "2_2") (pintype "passive"))
      (node (ref "SW_3") (pin "A") (pinfunction "A_A") (pintype "passive"))
    )
    (net (code "27") (name "/GPB5") (class "Default")
      (node (ref "C1_E1") (pin "1") (pinfunction "1_1") (pintype "passive"))
      (node (ref "MCP1") (pin "6") (pinfunction "GPB5_6") (pintype "bidirectional"))
      (node (ref "R1_E1") (pin "2") (pinfunction "2_2") (pintype "passive"))
      (node (ref "SW_1") (pin "1") (pinfunction "A_1") (pintype "bidirectional"))
    )
    (net (code "28") (name "/GPB6") (class "Default")
      (node (ref "C1_3") (pin "1") (pinfunction "1_1") (pintype "passive"))
      (node (ref "MCP1") (pin "7") (pinfunction "GPB6_7") (pintype "bidirectional"))
      (node (ref "R1_E3") (pin "2") (pinfunction "2_2") (pintype "passive"))
      (node (ref "SW_3") (pin "B") (pinfunction "B_B") (pintype "passive"))
    )
    (net (code "29") (name "/GPB7") (class "Default")
      (node (ref "C2_E1") (pin "1") (pinfunction "1_1") (pintype "passive"))
      (node (ref "MCP1") (pin "8") (pinfunction "GPB7_8") (pintype "bidirectional"))
      (node (ref "R2_E1") (pin "2") (pinfunction "2_2") (pintype "passive"))
      (node (ref "SW_1") (pin "3") (pinfunction "B_3") (pintype "bidirectional"))
    )
    (net (code "30") (name "/INTA") (class "Default")
      (node (ref "CONN_RPI") (pin "2") (pinfunction "KL_2") (pintype "passive"))
      (node (ref "CONN_RPI2") (pin "12") (pinfunction "KL_12") (pintype "passive"))
      (node (ref "JP_MCPINT_RPI") (pin "1") (pinfunction "1_1") (pintype "passive"))
    )
    (net (code "31") (name "/INTB") (class "Default")
      (node (ref "CONN_RPI") (pin "4") (pinfunction "KL_4") (pintype "passive"))
      (node (ref "CONN_RPI2") (pin "10") (pinfunction "KL_10") (pintype "passive"))
      (node (ref "JP_MCPINT_RPI") (pin "2") (pinfunction "2_2") (pintype "passive"))
    )
    (net (code "32") (name "/INTC") (class "Default")
      (node (ref "CONN_RPI") (pin "6") (pinfunction "KL_6") (pintype "passive"))
      (node (ref "CONN_RPI2") (pin "8") (pinfunction "KL_8") (pintype "passive"))
      (node (ref "JP_MCPINT_RPI") (pin "3") (pinfunction "3_3") (pintype "passive"))
    )
    (net (code "33") (name "/INTD") (class "Default")
      (node (ref "CONN_RPI") (pin "8") (pinfunction "KL_8") (pintype "passive"))
      (node (ref "CONN_RPI2") (pin "6") (pinfunction "KL_6") (pintype "passive"))
      (node (ref "JP_MCPINT_RPI") (pin "4") (pinfunction "4_4") (pintype "passive"))
    )
    (net (code "34") (name "/INTE") (class "Default")
      (node (ref "CONN_RPI") (pin "10") (pinfunction "KL_10") (pintype "passive"))
      (node (ref "CONN_RPI2") (pin "4") (pinfunction "KL_4") (pintype "passive"))
      (node (ref "JP_MCPINT_RPI") (pin "5") (pinfunction "5_5") (pintype "passive"))
    )
    (net (code "35") (name "/INTF") (class "Default")
      (node (ref "CONN_RPI") (pin "12") (pinfunction "KL_12") (pintype "passive"))
      (node (ref "CONN_RPI2") (pin "2") (pinfunction "KL_2") (pintype "passive"))
      (node (ref "JP_MCPINT_RPI") (pin "6") (pinfunction "6_6") (pintype "passive"))
    )
    (net (code "36") (name "/INT_MCP23017_1") (class "Default")
      (node (ref "JP_MCPINT_RPI") (pin "7") (pinfunction "7_7") (pintype "passive"))
      (node (ref "MCP1") (pin "20") (pinfunction "INTA_20") (pintype "output"))
    )
    (net (code "37") (name "/RST_MCP") (class "Default")
      (node (ref "CONN_RPI") (pin "9") (pinfunction "KL_9") (pintype "passive"))
      (node (ref "CONN_RPI2") (pin "9") (pinfunction "KL_9") (pintype "passive"))
      (node (ref "MCP1") (pin "18") (pinfunction "~{RESET}_18") (pintype "input"))
      (node (ref "R_RST_MCP23017") (pin "2") (pinfunction "2_2") (pintype "passive"))
    )
    (net (code "38") (name "/SCL") (class "Default")
      (node (ref "CONN_RPI") (pin "7") (pinfunction "KL_7") (pintype "passive"))
      (node (ref "CONN_RPI2") (pin "7") (pinfunction "KL_7") (pintype "passive"))
      (node (ref "CON_IS31_B") (pin "3") (pinfunction "3_3") (pintype "passive"))
      (node (ref "MCP1") (pin "12") (pinfunction "SCL_12") (pintype "input"))
    )
    (net (code "39") (name "/SDA") (class "Default")
      (node (ref "CONN_RPI") (pin "5") (pinfunction "KL_5") (pintype "passive"))
      (node (ref "CONN_RPI2") (pin "5") (pinfunction "KL_5") (pintype "passive"))
      (node (ref "CON_IS31_B") (pin "4") (pinfunction "4_4") (pintype "passive"))
      (node (ref "MCP1") (pin "13") (pinfunction "SDA_13") (pintype "bidirectional"))
    )
    (net (code "40") (name "GND") (class "Default")
      (node (ref "1-C1-MCP") (pin "2") (pinfunction "2_2") (pintype "passive"))
      (node (ref "1-C2_MCP") (pin "-") (pinfunction "-_-") (pintype "passive"))
      (node (ref "C1_3") (pin "2") (pinfunction "2_2") (pintype "passive"))
      (node (ref "C1_E1") (pin "2") (pinfunction "2_2") (pintype "passive"))
      (node (ref "C1_E2") (pin "2") (pinfunction "2_2") (pintype "passive"))
      (node (ref "C1_E4") (pin "2") (pinfunction "2_2") (pintype "passive"))
      (node (ref "C1_E5") (pin "2") (pinfunction "2_2") (pintype "passive"))
      (node (ref "C1_E6") (pin "2") (pinfunction "2_2") (pintype "passive"))
      (node (ref "C2_3") (pin "2") (pinfunction "2_2") (pintype "passive"))
      (node (ref "C2_E1") (pin "2") (pinfunction "2_2") (pintype "passive"))
      (node (ref "C2_E2") (pin "2") (pinfunction "2_2") (pintype "passive"))
      (node (ref "C2_E4") (pin "2") (pinfunction "2_2") (pintype "passive"))
      (node (ref "C2_E5") (pin "2") (pinfunction "2_2") (pintype "passive"))
      (node (ref "C2_E6") (pin "2") (pinfunction "2_2") (pintype "passive"))
      (node (ref "C3_3") (pin "2") (pinfunction "2_2") (pintype "passive"))
      (node (ref "C3_E4") (pin "2") (pinfunction "2_2") (pintype "passive"))
      (node (ref "C3_E5") (pin "2") (pinfunction "2_2") (pintype "passive"))
      (node (ref "C3_E6") (pin "2") (pinfunction "2_2") (pintype "passive"))
      (node (ref "CONN_RPI") (pin "1") (pinfunction "KL_1") (pintype "passive"))
      (node (ref "CONN_RPI") (pin "3") (pinfunction "KL_3") (pintype "passive"))
      (node (ref "CONN_RPI2") (pin "1") (pinfunction "KL_1") (pintype "passive"))
      (node (ref "CONN_RPI2") (pin "3") (pinfunction "KL_3") (pintype "passive"))
      (node (ref "CON_IS31_B") (pin "2") (pinfunction "2_2") (pintype "passive"))
      (node (ref "MCP1") (pin "10") (pinfunction "VSS_10") (pintype "power_in"))
      (node (ref "RDIS") (pin "2") (pinfunction "2_2") (pintype "passive"))
      (node (ref "R_A0") (pin "1") (pinfunction "1_1") (pintype "passive"))
      (node (ref "R_A1") (pin "1") (pinfunction "1_1") (pintype "passive"))
      (node (ref "R_A2") (pin "1") (pinfunction "1_1") (pintype "passive"))
    )
    (net (code "41") (name "VCC") (class "Default")
      (node (ref "1-C1-MCP") (pin "1") (pinfunction "1_1") (pintype "passive"))
      (node (ref "1-C2_MCP") (pin "+") (pinfunction "+_+") (pintype "passive"))
      (node (ref "CONN_RPI") (pin "11") (pinfunction "KL_11") (pintype "passive"))
      (node (ref "CONN_RPI") (pin "13") (pinfunction "KL_13") (pintype "passive"))
      (node (ref "CONN_RPI2") (pin "11") (pinfunction "KL_11") (pintype "passive"))
      (node (ref "CONN_RPI2") (pin "13") (pinfunction "KL_13") (pintype "passive"))
      (node (ref "CON_IS31_B") (pin "1") (pinfunction "1_1") (pintype "passive"))
      (node (ref "MCP1") (pin "9") (pinfunction "VDD_9") (pintype "power_in"))
      (node (ref "R1_E1") (pin "1") (pinfunction "1_1") (pintype "passive"))
      (node (ref "R1_E2") (pin "1") (pinfunction "1_1") (pintype "passive"))
      (node (ref "R1_E3") (pin "1") (pinfunction "1_1") (pintype "passive"))
      (node (ref "R1_E4") (pin "1") (pinfunction "1_1") (pintype "passive"))
      (node (ref "R1_E5") (pin "1") (pinfunction "1_1") (pintype "passive"))
      (node (ref "R1_E6") (pin "1") (pinfunction "1_1") (pintype "passive"))
      (node (ref "R2_E1") (pin "1") (pinfunction "1_1") (pintype "passive"))
      (node (ref "R2_E2") (pin "1") (pinfunction "1_1") (pintype "passive"))
      (node (ref "R2_E3") (pin "1") (pinfunction "1_1") (pintype "passive"))
      (node (ref "R2_E4") (pin "1") (pinfunction "1_1") (pintype "passive"))
      (node (ref "R2_E5") (pin "1") (pinfunction "1_1") (pintype "passive"))
      (node (ref "R2_E6") (pin "1") (pinfunction "1_1") (pintype "passive"))
      (node (ref "R3_E3") (pin "1") (pinfunction "1_1") (pintype "passive"))
      (node (ref "R3_E4") (pin "1") (pinfunction "1_1") (pintype "passive"))
      (node (ref "R3_E5") (pin "1") (pinfunction "1_1") (pintype "passive"))
      (node (ref "R3_E6") (pin "1") (pinfunction "1_1") (pintype "passive"))
      (node (ref "R_RST_MCP23017") (pin "1") (pinfunction "1_1") (pintype "passive"))
      (node (ref "SV1") (pin "2") (pinfunction "2_2") (pintype "passive"))
      (node (ref "SV1") (pin "4") (pinfunction "4_4") (pintype "passive"))
      (node (ref "SV1") (pin "6") (pinfunction "6_6") (pintype "passive"))
    )
    (net (code "42") (name "unconnected-(CONN_RPI2F-KL-Pad14)") (class "Default")
      (node (ref "CONN_RPI2") (pin "14") (pinfunction "KL_14") (pintype "passive"))
    )
    (net (code "43") (name "unconnected-(CONN_RPIF-KL-Pad14)") (class "Default")
      (node (ref "CONN_RPI") (pin "14") (pinfunction "KL_14") (pintype "passive"))
    )
    (net (code "44") (name "unconnected-(CON_IS31_A-Pad10)") (class "Default")
      (node (ref "CON_IS31_A") (pin "10") (pinfunction "10_10") (pintype "passive"))
    )
    (net (code "45") (name "unconnected-(CON_IS31_A-Pad11)") (class "Default")
      (node (ref "CON_IS31_A") (pin "11") (pinfunction "11_11") (pintype "passive"))
    )
    (net (code "46") (name "unconnected-(CON_IS31_A-Pad12)") (class "Default")
      (node (ref "CON_IS31_A") (pin "12") (pinfunction "12_12") (pintype "passive"))
    )
    (net (code "47") (name "unconnected-(CON_IS31_A-Pad13)") (class "Default")
      (node (ref "CON_IS31_A") (pin "13") (pinfunction "13_13") (pintype "passive"))
    )
    (net (code "48") (name "unconnected-(MCP1-INTB-Pad19)") (class "Default")
      (node (ref "MCP1") (pin "19") (pinfunction "INTB_19") (pintype "output"))
    )
  )
)
